# schematic_V2.net
KiCad netlist of a schematic drawn in EAGLE
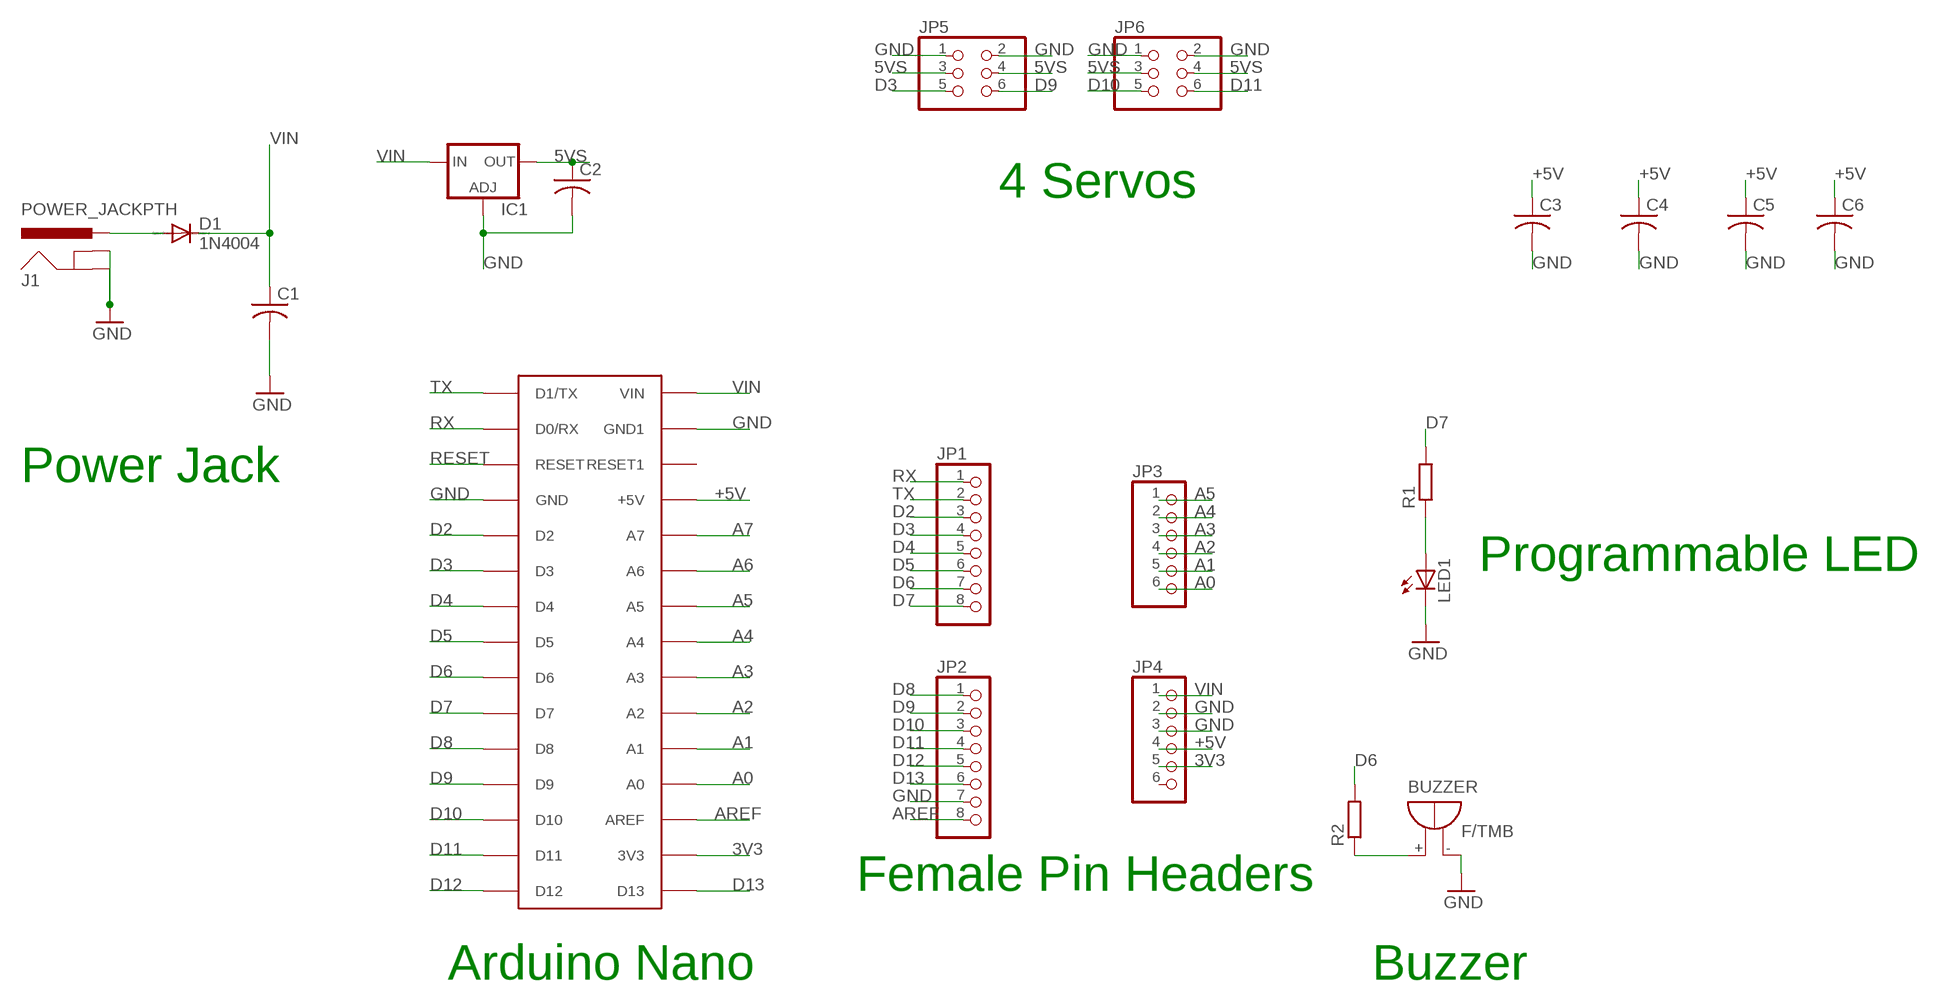
[diagram p0: schematic, sheet 1]

(export (version "E")
  (design (tool "Eeschema 10.0.6"))
  (components
    (comp (ref "BUZZER")
      (value "F/TMB")
      (footprint "eagle-import:F_TMB")
      (libsource (lib "eagle-import") (part "F/TMB"))
    )
    (comp (ref "C1")
      (value "C-USC1206")
      (footprint "eagle-import:C1206")
      (libsource (lib "eagle-import") (part "C-USC1206"))
    )
    (comp (ref "C2")
      (value "C-USC1206")
      (footprint "eagle-import:C1206")
      (libsource (lib "eagle-import") (part "C-USC1206"))
    )
    (comp (ref "C3")
      (value "C-USC1206")
      (footprint "eagle-import:C1206")
      (libsource (lib "eagle-import") (part "C-USC1206"))
    )
    (comp (ref "C4")
      (value "C-USC1206")
      (footprint "eagle-import:C1206")
      (libsource (lib "eagle-import") (part "C-USC1206"))
    )
    (comp (ref "C5")
      (value "C-USC1206")
      (footprint "eagle-import:C1206")
      (libsource (lib "eagle-import") (part "C-USC1206"))
    )
    (comp (ref "C6")
      (value "C-USC1206")
      (footprint "eagle-import:C1206")
      (libsource (lib "eagle-import") (part "C-USC1206"))
    )
    (comp (ref "D1")
      (value "1N4004")
      (footprint "eagle-import:DO41-10")
      (libsource (lib "eagle-import") (part "1N4004"))
    )
    (comp (ref "IC1")
      (value "LD117AS33TR")
      (footprint "eagle-import:SOT223")
      (libsource (lib "eagle-import") (part "LD117A?S33TR"))
    )
    (comp (ref "J1")
      (value "POWER_JACKPTH")
      (footprint "eagle-import:POWER_JACK_PTH")
      (libsource (lib "eagle-import") (part "POWER_JACKPTH"))
    )
    (comp (ref "JP1")
      (value "PINHD-1X8")
      (footprint "eagle-import:1X08")
      (libsource (lib "eagle-import") (part "PINHD-1X8"))
    )
    (comp (ref "JP2")
      (value "PINHD-1X8")
      (footprint "eagle-import:1X08")
      (libsource (lib "eagle-import") (part "PINHD-1X8"))
    )
    (comp (ref "JP3")
      (value "PINHD-1X6")
      (footprint "eagle-import:1X06")
      (libsource (lib "eagle-import") (part "PINHD-1X6"))
    )
    (comp (ref "JP4")
      (value "PINHD-1X6")
      (footprint "eagle-import:1X06")
      (libsource (lib "eagle-import") (part "PINHD-1X6"))
    )
    (comp (ref "JP5")
      (value "PINHD-2X3")
      (footprint "eagle-import:2X03")
      (libsource (lib "eagle-import") (part "PINHD-2X3"))
    )
    (comp (ref "JP6")
      (value "PINHD-2X3")
      (footprint "eagle-import:2X03")
      (libsource (lib "eagle-import") (part "PINHD-2X3"))
    )
    (comp (ref "LED1")
      (value "LED5MM")
      (footprint "eagle-import:LED5MM")
      (libsource (lib "eagle-import") (part "LED5MM"))
    )
    (comp (ref "R1")
      (value "R-EU_0207/10")
      (footprint "eagle-import:0207_10")
      (libsource (lib "eagle-import") (part "R-EU_0207/10"))
    )
    (comp (ref "R2")
      (value "R-EU_0207/10")
      (footprint "eagle-import:0207_10")
      (libsource (lib "eagle-import") (part "R-EU_0207/10"))
    )
    (comp (ref "U$1")
      (value "ARDUINONANO")
      (footprint "eagle-import:PDIP-32")
      (libsource (lib "eagle-import") (part "ARDUINONANO"))
    )
  )
  (nets
    (net (code "1") (name "/+5V") (class "Default")
      (node (ref "C3") (pin "1") (pinfunction "1_1") (pintype "passive"))
      (node (ref "C4") (pin "1") (pinfunction "1_1") (pintype "passive"))
      (node (ref "C5") (pin "1") (pinfunction "1_1") (pintype "passive"))
      (node (ref "C6") (pin "1") (pinfunction "1_1") (pintype "passive"))
      (node (ref "JP4") (pin "4") (pinfunction "4_4") (pintype "passive"))
      (node (ref "U$1") (pin "+5V") (pinfunction "+5V_+5V") (pintype "bidirectional"))
    )
    (net (code "2") (name "/3V3") (class "Default")
      (node (ref "JP4") (pin "5") (pinfunction "5_5") (pintype "passive"))
      (node (ref "U$1") (pin "3V3") (pinfunction "3V3_3V3") (pintype "bidirectional"))
    )
    (net (code "3") (name "/5VS") (class "Default")
      (node (ref "C2") (pin "1") (pinfunction "1_1") (pintype "passive"))
      (node (ref "IC1") (pin "4") (pinfunction "OUT_4") (pintype "passive"))
      (node (ref "JP5") (pin "3") (pinfunction "3_3") (pintype "passive"))
      (node (ref "JP5") (pin "4") (pinfunction "4_4") (pintype "passive"))
      (node (ref "JP6") (pin "3") (pinfunction "3_3") (pintype "passive"))
      (node (ref "JP6") (pin "4") (pinfunction "4_4") (pintype "passive"))
    )
    (net (code "4") (name "/A0") (class "Default")
      (node (ref "JP3") (pin "6") (pinfunction "6_6") (pintype "passive"))
      (node (ref "U$1") (pin "A7") (pinfunction "A0_A7") (pintype "bidirectional"))
    )
    (net (code "5") (name "/A1") (class "Default")
      (node (ref "JP3") (pin "5") (pinfunction "5_5") (pintype "passive"))
      (node (ref "U$1") (pin "A6") (pinfunction "A1_A6") (pintype "bidirectional"))
    )
    (net (code "6") (name "/A2") (class "Default")
      (node (ref "JP3") (pin "4") (pinfunction "4_4") (pintype "passive"))
      (node (ref "U$1") (pin "A5") (pinfunction "A2_A5") (pintype "bidirectional"))
    )
    (net (code "7") (name "/A3") (class "Default")
      (node (ref "JP3") (pin "3") (pinfunction "3_3") (pintype "passive"))
      (node (ref "U$1") (pin "A4") (pinfunction "A3_A4") (pintype "bidirectional"))
    )
    (net (code "8") (name "/A4") (class "Default")
      (node (ref "JP3") (pin "2") (pinfunction "2_2") (pintype "passive"))
      (node (ref "U$1") (pin "A3") (pinfunction "A4_A3") (pintype "bidirectional"))
    )
    (net (code "9") (name "/A5") (class "Default")
      (node (ref "JP3") (pin "1") (pinfunction "1_1") (pintype "passive"))
      (node (ref "U$1") (pin "A2") (pinfunction "A5_A2") (pintype "bidirectional"))
    )
    (net (code "10") (name "/A6") (class "Default")
      (node (ref "U$1") (pin "A1") (pinfunction "A6_A1") (pintype "bidirectional"))
    )
    (net (code "11") (name "/A7") (class "Default")
      (node (ref "U$1") (pin "A0") (pinfunction "A7_A0") (pintype "bidirectional"))
    )
    (net (code "12") (name "/AREF") (class "Default")
      (node (ref "JP2") (pin "8") (pinfunction "8_8") (pintype "passive"))
      (node (ref "U$1") (pin "AREF") (pinfunction "AREF_AREF") (pintype "bidirectional"))
    )
    (net (code "13") (name "/D2") (class "Default")
      (node (ref "JP1") (pin "3") (pinfunction "3_3") (pintype "passive"))
      (node (ref "U$1") (pin "D2") (pinfunction "D2_D2") (pintype "bidirectional"))
    )
    (net (code "14") (name "/D3") (class "Default")
      (node (ref "JP1") (pin "4") (pinfunction "4_4") (pintype "passive"))
      (node (ref "JP5") (pin "5") (pinfunction "5_5") (pintype "passive"))
      (node (ref "U$1") (pin "D3") (pinfunction "D3_D3") (pintype "bidirectional"))
    )
    (net (code "15") (name "/D4") (class "Default")
      (node (ref "JP1") (pin "5") (pinfunction "5_5") (pintype "passive"))
      (node (ref "U$1") (pin "D4") (pinfunction "D4_D4") (pintype "bidirectional"))
    )
    (net (code "16") (name "/D5") (class "Default")
      (node (ref "JP1") (pin "6") (pinfunction "6_6") (pintype "passive"))
      (node (ref "U$1") (pin "D5") (pinfunction "D5_D5") (pintype "bidirectional"))
    )
    (net (code "17") (name "/D6") (class "Default")
      (node (ref "JP1") (pin "7") (pinfunction "7_7") (pintype "passive"))
      (node (ref "R2") (pin "2") (pinfunction "2_2") (pintype "passive"))
      (node (ref "U$1") (pin "D6") (pinfunction "D6_D6") (pintype "bidirectional"))
    )
    (net (code "18") (name "/D7") (class "Default")
      (node (ref "JP1") (pin "8") (pinfunction "8_8") (pintype "passive"))
      (node (ref "R1") (pin "2") (pinfunction "2_2") (pintype "passive"))
      (node (ref "U$1") (pin "D7") (pinfunction "D7_D7") (pintype "bidirectional"))
    )
    (net (code "19") (name "/D8") (class "Default")
      (node (ref "JP2") (pin "1") (pinfunction "1_1") (pintype "passive"))
      (node (ref "U$1") (pin "D8") (pinfunction "D8_D8") (pintype "bidirectional"))
    )
    (net (code "20") (name "/D9") (class "Default")
      (node (ref "JP2") (pin "2") (pinfunction "2_2") (pintype "passive"))
      (node (ref "JP5") (pin "6") (pinfunction "6_6") (pintype "passive"))
      (node (ref "U$1") (pin "D9") (pinfunction "D9_D9") (pintype "bidirectional"))
    )
    (net (code "21") (name "/D10") (class "Default")
      (node (ref "JP2") (pin "3") (pinfunction "3_3") (pintype "passive"))
      (node (ref "JP6") (pin "5") (pinfunction "5_5") (pintype "passive"))
      (node (ref "U$1") (pin "D10") (pinfunction "D10_D10") (pintype "bidirectional"))
    )
    (net (code "22") (name "/D11") (class "Default")
      (node (ref "JP2") (pin "4") (pinfunction "4_4") (pintype "passive"))
      (node (ref "JP6") (pin "6") (pinfunction "6_6") (pintype "passive"))
      (node (ref "U$1") (pin "D11") (pinfunction "D11_D11") (pintype "bidirectional"))
    )
    (net (code "23") (name "/D12") (class "Default")
      (node (ref "JP2") (pin "5") (pinfunction "5_5") (pintype "passive"))
      (node (ref "U$1") (pin "D12") (pinfunction "D12_D12") (pintype "bidirectional"))
    )
    (net (code "24") (name "/D13") (class "Default")
      (node (ref "JP2") (pin "6") (pinfunction "6_6") (pintype "passive"))
      (node (ref "U$1") (pin "D13") (pinfunction "D13_D13") (pintype "bidirectional"))
    )
    (net (code "25") (name "/RESET") (class "Default")
      (node (ref "U$1") (pin "RESET") (pinfunction "RESET_RESET") (pintype "bidirectional"))
    )
    (net (code "26") (name "/RX") (class "Default")
      (node (ref "JP1") (pin "1") (pinfunction "1_1") (pintype "passive"))
      (node (ref "U$1") (pin "D0/RX") (pinfunction "D0/RX_D0/RX") (pintype "bidirectional"))
    )
    (net (code "27") (name "/TX") (class "Default")
      (node (ref "JP1") (pin "2") (pinfunction "2_2") (pintype "passive"))
      (node (ref "U$1") (pin "D1/TX") (pinfunction "D1/TX_D1/TX") (pintype "bidirectional"))
    )
    (net (code "28") (name "/VIN") (class "Default")
      (node (ref "C1") (pin "1") (pinfunction "1_1") (pintype "passive"))
      (node (ref "D1") (pin "C") (pinfunction "C_C") (pintype "passive"))
      (node (ref "IC1") (pin "3") (pinfunction "IN_3") (pintype "input"))
      (node (ref "JP4") (pin "1") (pinfunction "1_1") (pintype "passive"))
      (node (ref "U$1") (pin "VIN") (pinfunction "VIN_VIN") (pintype "bidirectional"))
    )
    (net (code "29") (name "GND") (class "Default")
      (node (ref "BUZZER") (pin "-") (pinfunction "-_-") (pintype "passive"))
      (node (ref "C1") (pin "2") (pinfunction "2_2") (pintype "passive"))
      (node (ref "C2") (pin "2") (pinfunction "2_2") (pintype "passive"))
      (node (ref "C3") (pin "2") (pinfunction "2_2") (pintype "passive"))
      (node (ref "C4") (pin "2") (pinfunction "2_2") (pintype "passive"))
      (node (ref "C5") (pin "2") (pinfunction "2_2") (pintype "passive"))
      (node (ref "C6") (pin "2") (pinfunction "2_2") (pintype "passive"))
      (node (ref "IC1") (pin "1") (pinfunction "ADJ_1") (pintype "input"))
      (node (ref "J1") (pin "GND") (pinfunction "GND_GND") (pintype "bidirectional"))
      (node (ref "J1") (pin "GNDBREAK") (pinfunction "GNDBREAK_GNDBREAK") (pintype "bidirectional"))
      (node (ref "JP2") (pin "7") (pinfunction "7_7") (pintype "passive"))
      (node (ref "JP4") (pin "2") (pinfunction "2_2") (pintype "passive"))
      (node (ref "JP4") (pin "3") (pinfunction "3_3") (pintype "passive"))
      (node (ref "JP5") (pin "1") (pinfunction "1_1") (pintype "passive"))
      (node (ref "JP5") (pin "2") (pinfunction "2_2") (pintype "passive"))
      (node (ref "JP6") (pin "1") (pinfunction "1_1") (pintype "passive"))
      (node (ref "JP6") (pin "2") (pinfunction "2_2") (pintype "passive"))
      (node (ref "LED1") (pin "K") (pinfunction "C_K") (pintype "passive"))
      (node (ref "U$1") (pin "GND") (pinfunction "GND_GND") (pintype "bidirectional"))
      (node (ref "U$1") (pin "GND1") (pinfunction "GND1_GND1") (pintype "bidirectional"))
    )
    (net (code "30") (name "Net-(BUZZER-Pad+)") (class "Default")
      (node (ref "BUZZER") (pin "+") (pinfunction "+_+") (pintype "passive"))
      (node (ref "R2") (pin "1") (pinfunction "1_1") (pintype "passive"))
    )
    (net (code "31") (name "Net-(D1-PadA)") (class "Default")
      (node (ref "D1") (pin "A") (pinfunction "A_A") (pintype "passive"))
      (node (ref "J1") (pin "PWR") (pinfunction "PWR_PWR") (pintype "bidirectional"))
    )
    (net (code "32") (name "Net-(LED1-PadA)") (class "Default")
      (node (ref "LED1") (pin "A") (pinfunction "A_A") (pintype "passive"))
      (node (ref "R1") (pin "1") (pinfunction "1_1") (pintype "passive"))
    )
    (net (code "33") (name "unconnected-(JP4-Pad6)") (class "Default")
      (node (ref "JP4") (pin "6") (pinfunction "6_6") (pintype "passive"))
    )
    (net (code "34") (name "unconnected-(U$1-PadRESET1)") (class "Default")
      (node (ref "U$1") (pin "RESET1") (pinfunction "RESET1_RESET1") (pintype "bidirectional"))
    )
  )
)
